# IC_common.net
KiCad netlist of a schematic drawn in Altium Designer
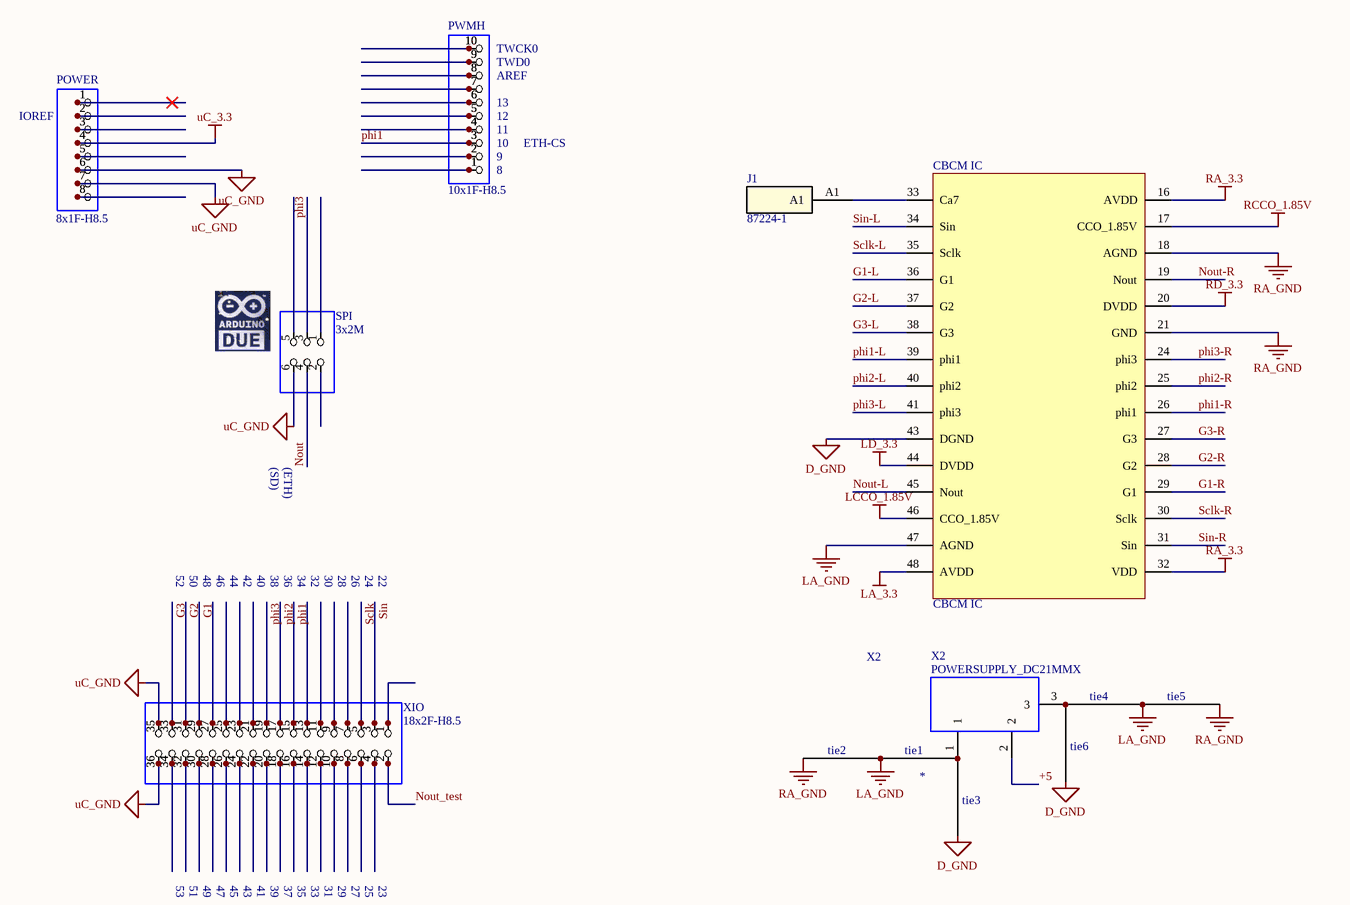
[diagram p0: IC common.SchDoc]

(export (version "E")
  (design (tool "Eeschema 10.0.6"))
  (components
    (comp (ref "CBCM IC")
      (value "CBCM IC")
      (footprint "PGA85x11")
      (libsource (lib "CBCM IC") (part "CBCM IC"))
    )
    (comp (ref "J1")
      (value "87224-1")
      (footprint "87224-1")
      (description "Imported")
      (libsource (lib "SINGLE pin") (part "87224-1"))
    )
    (comp (ref "POWER")
      (value "8x1F-H8.5")
      (footprint "1X08")
      (libsource (lib "SmartPrj") (part "PINHD-1X8"))
    )
    (comp (ref "PWMH")
      (value "10x1F-H8.5")
      (footprint "1X10")
      (libsource (lib "SmartPrj") (part "PINHD-1X10"))
    )
    (comp (ref "SPI") (value "3x2M") (footprint "2X03") (libsource (lib "SmartPrj") (part "PINHD-2X3")))
    (comp (ref "tie1") (value "Net Tie") (footprint "net_tie") (libsource (lib "Net Tie") (part "Net Tie")))
    (comp (ref "tie2") (value "Net Tie") (footprint "net_tie") (libsource (lib "Net Tie") (part "Net Tie")))
    (comp (ref "tie3") (value "Net Tie") (footprint "net_tie") (libsource (lib "Net Tie") (part "Net Tie")))
    (comp (ref "tie4") (value "Net Tie") (footprint "net_tie") (libsource (lib "Net Tie") (part "Net Tie")))
    (comp (ref "tie5") (value "Net Tie") (footprint "net_tie") (libsource (lib "Net Tie") (part "Net Tie")))
    (comp (ref "tie6") (value "Net Tie") (footprint "net_tie") (libsource (lib "Net Tie") (part "Net Tie")))
    (comp (ref "X2")
      (value "*")
      (footprint "POWERSUPPLY_DC-21MM")
      (libsource (lib "SmartPrj") (part "POWERSUPPLY_DC21MMX"))
    )
    (comp (ref "XIO")
      (value "18x2F-H8.5")
      (footprint "2X18")
      (libsource (lib "SmartPrj") (part "PINHD-2X18"))
    )
  )
  (nets
    (net (code "1") (name "/+5") (class "Default")
      (node (ref "X2") (pin "2") (pinfunction "2_2") (pintype "passive"))
    )
    (net (code "2") (name "/G1") (class "Default")
      (node (ref "XIO") (pin "29") (pinfunction "29_29") (pintype "passive"))
    )
    (net (code "3") (name "/G1-L") (class "Default")
      (node (ref "CBCM IC") (pin "36") (pinfunction "G1_36") (pintype "passive"))
    )
    (net (code "4") (name "/G1-R") (class "Default")
      (node (ref "CBCM IC") (pin "29") (pinfunction "G1_29") (pintype "passive"))
    )
    (net (code "5") (name "/G2") (class "Default")
      (node (ref "XIO") (pin "31") (pinfunction "31_31") (pintype "passive"))
    )
    (net (code "6") (name "/G2-L") (class "Default")
      (node (ref "CBCM IC") (pin "37") (pinfunction "G2_37") (pintype "passive"))
    )
    (net (code "7") (name "/G2-R") (class "Default")
      (node (ref "CBCM IC") (pin "28") (pinfunction "G2_28") (pintype "passive"))
    )
    (net (code "8") (name "/G3") (class "Default")
      (node (ref "XIO") (pin "33") (pinfunction "33_33") (pintype "passive"))
    )
    (net (code "9") (name "/G3-L") (class "Default")
      (node (ref "CBCM IC") (pin "38") (pinfunction "G3_38") (pintype "passive"))
    )
    (net (code "10") (name "/G3-R") (class "Default")
      (node (ref "CBCM IC") (pin "27") (pinfunction "G3_27") (pintype "passive"))
    )
    (net (code "11") (name "/Nout") (class "Default")
      (node (ref "SPI") (pin "4") (pinfunction "4_4") (pintype "passive"))
    )
    (net (code "12") (name "/Nout-L") (class "Default")
      (node (ref "CBCM IC") (pin "45") (pinfunction "Nout_45") (pintype "passive"))
    )
    (net (code "13") (name "/Nout-R") (class "Default")
      (node (ref "CBCM IC") (pin "19") (pinfunction "Nout_19") (pintype "passive"))
    )
    (net (code "14") (name "/Nout_test") (class "Default")
      (node (ref "XIO") (pin "2") (pinfunction "2_2") (pintype "passive"))
    )
    (net (code "15") (name "/Sclk") (class "Default")
      (node (ref "XIO") (pin "5") (pinfunction "5_5") (pintype "passive"))
    )
    (net (code "16") (name "/Sclk-L") (class "Default")
      (node (ref "CBCM IC") (pin "35") (pinfunction "Sclk_35") (pintype "passive"))
    )
    (net (code "17") (name "/Sclk-R") (class "Default")
      (node (ref "CBCM IC") (pin "30") (pinfunction "Sclk_30") (pintype "passive"))
    )
    (net (code "18") (name "/Sin") (class "Default")
      (node (ref "XIO") (pin "3") (pinfunction "3_3") (pintype "passive"))
    )
    (net (code "19") (name "/Sin-L") (class "Default")
      (node (ref "CBCM IC") (pin "34") (pinfunction "Sin_34") (pintype "passive"))
    )
    (net (code "20") (name "/Sin-R") (class "Default")
      (node (ref "CBCM IC") (pin "31") (pinfunction "Sin_31") (pintype "passive"))
    )
    (net (code "21") (name "/phi1") (class "Default")
      (node (ref "PWMH") (pin "3") (pinfunction "3_3") (pintype "passive"))
      (node (ref "XIO") (pin "15") (pinfunction "15_15") (pintype "passive"))
    )
    (net (code "22") (name "/phi1-L") (class "Default")
      (node (ref "CBCM IC") (pin "39") (pinfunction "phi1_39") (pintype "passive"))
    )
    (net (code "23") (name "/phi1-R") (class "Default")
      (node (ref "CBCM IC") (pin "26") (pinfunction "phi1_26") (pintype "passive"))
    )
    (net (code "24") (name "/phi2") (class "Default")
      (node (ref "XIO") (pin "17") (pinfunction "17_17") (pintype "passive"))
    )
    (net (code "25") (name "/phi2-L") (class "Default")
      (node (ref "CBCM IC") (pin "40") (pinfunction "phi2_40") (pintype "passive"))
    )
    (net (code "26") (name "/phi2-R") (class "Default")
      (node (ref "CBCM IC") (pin "25") (pinfunction "phi2_25") (pintype "passive"))
    )
    (net (code "27") (name "/phi3") (class "Default")
      (node (ref "SPI") (pin "3") (pinfunction "3_3") (pintype "passive"))
      (node (ref "XIO") (pin "19") (pinfunction "19_19") (pintype "passive"))
    )
    (net (code "28") (name "/phi3-L") (class "Default")
      (node (ref "CBCM IC") (pin "41") (pinfunction "phi3_41") (pintype "passive"))
    )
    (net (code "29") (name "/phi3-R") (class "Default")
      (node (ref "CBCM IC") (pin "24") (pinfunction "phi3_24") (pintype "passive"))
    )
    (net (code "30") (name "D_GND") (class "Default")
      (node (ref "CBCM IC") (pin "43") (pinfunction "DGND_43") (pintype "passive"))
      (node (ref "tie3") (pin "0") (pinfunction "0_0") (pintype "passive"))
      (node (ref "tie6") (pin "0") (pinfunction "0_0") (pintype "passive"))
    )
    (net (code "31") (name "LA_3.3") (class "Default")
      (node (ref "CBCM IC") (pin "48") (pinfunction "AVDD_48") (pintype "power_in"))
    )
    (net (code "32") (name "LA_GND") (class "Default")
      (node (ref "CBCM IC") (pin "47") (pinfunction "AGND_47") (pintype "power_in"))
      (node (ref "tie1") (pin "0") (pinfunction "0_0") (pintype "passive"))
      (node (ref "tie2") (pin "1") (pinfunction "1_1") (pintype "passive"))
      (node (ref "tie4") (pin "1") (pinfunction "1_1") (pintype "passive"))
      (node (ref "tie5") (pin "0") (pinfunction "0_0") (pintype "passive"))
    )
    (net (code "33") (name "LCCO_1.85V") (class "Default")
      (node (ref "CBCM IC") (pin "46") (pinfunction "CCO_1.85V_46") (pintype "power_in"))
    )
    (net (code "34") (name "LD_3.3") (class "Default")
      (node (ref "CBCM IC") (pin "44") (pinfunction "DVDD_44") (pintype "power_in"))
    )
    (net (code "35") (name "Net-(CBCM IC-Ca7)") (class "Default")
      (node (ref "CBCM IC") (pin "33") (pinfunction "Ca7_33") (pintype "passive"))
      (node (ref "J1") (pin "A1") (pinfunction "A1_A1") (pintype "passive"))
    )
    (net (code "36") (name "Net-(POWER-Pad1)") (class "Default")
      (node (ref "POWER") (pin "1") (pinfunction "1_1") (pintype "passive"))
    )
    (net (code "37") (name "Net-(POWER-Pad2)") (class "Default")
      (node (ref "POWER") (pin "2") (pinfunction "2_2") (pintype "passive"))
    )
    (net (code "38") (name "Net-(POWER-Pad3)") (class "Default")
      (node (ref "POWER") (pin "3") (pinfunction "3_3") (pintype "passive"))
    )
    (net (code "39") (name "Net-(POWER-Pad5)") (class "Default")
      (node (ref "POWER") (pin "5") (pinfunction "5_5") (pintype "passive"))
    )
    (net (code "40") (name "Net-(POWER-Pad8)") (class "Default")
      (node (ref "POWER") (pin "8") (pinfunction "8_8") (pintype "passive"))
    )
    (net (code "41") (name "Net-(PWMH-Pad1)") (class "Default")
      (node (ref "PWMH") (pin "1") (pinfunction "1_1") (pintype "passive"))
    )
    (net (code "42") (name "Net-(PWMH-Pad2)") (class "Default")
      (node (ref "PWMH") (pin "2") (pinfunction "2_2") (pintype "passive"))
    )
    (net (code "43") (name "Net-(PWMH-Pad4)") (class "Default")
      (node (ref "PWMH") (pin "4") (pinfunction "4_4") (pintype "passive"))
    )
    (net (code "44") (name "Net-(PWMH-Pad5)") (class "Default")
      (node (ref "PWMH") (pin "5") (pinfunction "5_5") (pintype "passive"))
    )
    (net (code "45") (name "Net-(PWMH-Pad6)") (class "Default")
      (node (ref "PWMH") (pin "6") (pinfunction "6_6") (pintype "passive"))
    )
    (net (code "46") (name "Net-(PWMH-Pad7)") (class "Default")
      (node (ref "PWMH") (pin "7") (pinfunction "7_7") (pintype "passive"))
    )
    (net (code "47") (name "Net-(PWMH-Pad8)") (class "Default")
      (node (ref "PWMH") (pin "8") (pinfunction "8_8") (pintype "passive"))
    )
    (net (code "48") (name "Net-(PWMH-Pad9)") (class "Default")
      (node (ref "PWMH") (pin "9") (pinfunction "9_9") (pintype "passive"))
    )
    (net (code "49") (name "Net-(PWMH-Pad10)") (class "Default")
      (node (ref "PWMH") (pin "10") (pinfunction "10_10") (pintype "passive"))
    )
    (net (code "50") (name "Net-(X2-Pad1)") (class "Default")
      (node (ref "X2") (pin "1") (pinfunction "1_1") (pintype "passive"))
      (node (ref "tie1") (pin "1") (pinfunction "1_1") (pintype "passive"))
      (node (ref "tie3") (pin "1") (pinfunction "1_1") (pintype "passive"))
    )
    (net (code "51") (name "Net-(X2-Pad3)") (class "Default")
      (node (ref "X2") (pin "3") (pinfunction "3_3") (pintype "passive"))
      (node (ref "tie4") (pin "0") (pinfunction "0_0") (pintype "passive"))
      (node (ref "tie6") (pin "1") (pinfunction "1_1") (pintype "passive"))
    )
    (net (code "52") (name "Net-(XIO-Pad1)") (class "Default")
      (node (ref "XIO") (pin "1") (pinfunction "1_1") (pintype "passive"))
    )
    (net (code "53") (name "Net-(XIO-Pad4)") (class "Default")
      (node (ref "XIO") (pin "4") (pinfunction "4_4") (pintype "passive"))
    )
    (net (code "54") (name "Net-(XIO-Pad6)") (class "Default")
      (node (ref "XIO") (pin "6") (pinfunction "6_6") (pintype "passive"))
    )
    (net (code "55") (name "Net-(XIO-Pad7)") (class "Default")
      (node (ref "XIO") (pin "7") (pinfunction "7_7") (pintype "passive"))
    )
    (net (code "56") (name "Net-(XIO-Pad8)") (class "Default")
      (node (ref "XIO") (pin "8") (pinfunction "8_8") (pintype "passive"))
    )
    (net (code "57") (name "Net-(XIO-Pad9)") (class "Default")
      (node (ref "XIO") (pin "9") (pinfunction "9_9") (pintype "passive"))
    )
    (net (code "58") (name "Net-(XIO-Pad10)") (class "Default")
      (node (ref "XIO") (pin "10") (pinfunction "10_10") (pintype "passive"))
    )
    (net (code "59") (name "Net-(XIO-Pad11)") (class "Default")
      (node (ref "XIO") (pin "11") (pinfunction "11_11") (pintype "passive"))
    )
    (net (code "60") (name "Net-(XIO-Pad12)") (class "Default")
      (node (ref "XIO") (pin "12") (pinfunction "12_12") (pintype "passive"))
    )
    (net (code "61") (name "Net-(XIO-Pad13)") (class "Default")
      (node (ref "XIO") (pin "13") (pinfunction "13_13") (pintype "passive"))
    )
    (net (code "62") (name "Net-(XIO-Pad14)") (class "Default")
      (node (ref "XIO") (pin "14") (pinfunction "14_14") (pintype "passive"))
    )
    (net (code "63") (name "Net-(XIO-Pad16)") (class "Default")
      (node (ref "XIO") (pin "16") (pinfunction "16_16") (pintype "passive"))
    )
    (net (code "64") (name "Net-(XIO-Pad18)") (class "Default")
      (node (ref "XIO") (pin "18") (pinfunction "18_18") (pintype "passive"))
    )
    (net (code "65") (name "Net-(XIO-Pad20)") (class "Default")
      (node (ref "XIO") (pin "20") (pinfunction "20_20") (pintype "passive"))
    )
    (net (code "66") (name "Net-(XIO-Pad21)") (class "Default")
      (node (ref "XIO") (pin "21") (pinfunction "21_21") (pintype "passive"))
    )
    (net (code "67") (name "Net-(XIO-Pad22)") (class "Default")
      (node (ref "XIO") (pin "22") (pinfunction "22_22") (pintype "passive"))
    )
    (net (code "68") (name "Net-(XIO-Pad23)") (class "Default")
      (node (ref "XIO") (pin "23") (pinfunction "23_23") (pintype "passive"))
    )
    (net (code "69") (name "Net-(XIO-Pad24)") (class "Default")
      (node (ref "XIO") (pin "24") (pinfunction "24_24") (pintype "passive"))
    )
    (net (code "70") (name "Net-(XIO-Pad25)") (class "Default")
      (node (ref "XIO") (pin "25") (pinfunction "25_25") (pintype "passive"))
    )
    (net (code "71") (name "Net-(XIO-Pad26)") (class "Default")
      (node (ref "XIO") (pin "26") (pinfunction "26_26") (pintype "passive"))
    )
    (net (code "72") (name "Net-(XIO-Pad27)") (class "Default")
      (node (ref "XIO") (pin "27") (pinfunction "27_27") (pintype "passive"))
    )
    (net (code "73") (name "Net-(XIO-Pad28)") (class "Default")
      (node (ref "XIO") (pin "28") (pinfunction "28_28") (pintype "passive"))
    )
    (net (code "74") (name "Net-(XIO-Pad30)") (class "Default")
      (node (ref "XIO") (pin "30") (pinfunction "30_30") (pintype "passive"))
    )
    (net (code "75") (name "Net-(XIO-Pad32)") (class "Default")
      (node (ref "XIO") (pin "32") (pinfunction "32_32") (pintype "passive"))
    )
    (net (code "76") (name "Net-(XIO-Pad34)") (class "Default")
      (node (ref "XIO") (pin "34") (pinfunction "34_34") (pintype "passive"))
    )
    (net (code "77") (name "RA_3.3") (class "Default")
      (node (ref "CBCM IC") (pin "16") (pinfunction "AVDD_16") (pintype "power_in"))
      (node (ref "CBCM IC") (pin "32") (pinfunction "VDD_32") (pintype "power_in"))
    )
    (net (code "78") (name "RA_GND") (class "Default")
      (node (ref "CBCM IC") (pin "18") (pinfunction "AGND_18") (pintype "power_in"))
      (node (ref "CBCM IC") (pin "21") (pinfunction "GND_21") (pintype "power_in"))
      (node (ref "tie2") (pin "0") (pinfunction "0_0") (pintype "passive"))
      (node (ref "tie5") (pin "1") (pinfunction "1_1") (pintype "passive"))
    )
    (net (code "79") (name "RCCO_1.85V") (class "Default")
      (node (ref "CBCM IC") (pin "17") (pinfunction "CCO_1.85V_17") (pintype "power_in"))
    )
    (net (code "80") (name "RD_3.3") (class "Default")
      (node (ref "CBCM IC") (pin "20") (pinfunction "DVDD_20") (pintype "power_in"))
    )
    (net (code "81") (name "uC_3.3") (class "Default")
      (node (ref "POWER") (pin "4") (pinfunction "4_4") (pintype "passive"))
    )
    (net (code "82") (name "uC_GND") (class "Default")
      (node (ref "POWER") (pin "6") (pinfunction "6_6") (pintype "passive"))
      (node (ref "POWER") (pin "7") (pinfunction "7_7") (pintype "passive"))
      (node (ref "SPI") (pin "6") (pinfunction "6_6") (pintype "passive"))
      (node (ref "XIO") (pin "35") (pinfunction "35_35") (pintype "passive"))
      (node (ref "XIO") (pin "36") (pinfunction "36_36") (pintype "passive"))
    )
    (net (code "83") (name "unconnected-(SPI-Pad1)") (class "Default")
      (node (ref "SPI") (pin "1") (pinfunction "1_1") (pintype "passive"))
    )
    (net (code "84") (name "unconnected-(SPI-Pad2)") (class "Default")
      (node (ref "SPI") (pin "2") (pinfunction "2_2") (pintype "passive"))
    )
    (net (code "85") (name "unconnected-(SPI-Pad5)") (class "Default")
      (node (ref "SPI") (pin "5") (pinfunction "5_5") (pintype "passive"))
    )
  )
)
